# Cap_Sensor_Hand.net
KiCad netlist of a schematic drawn in Altium Designer
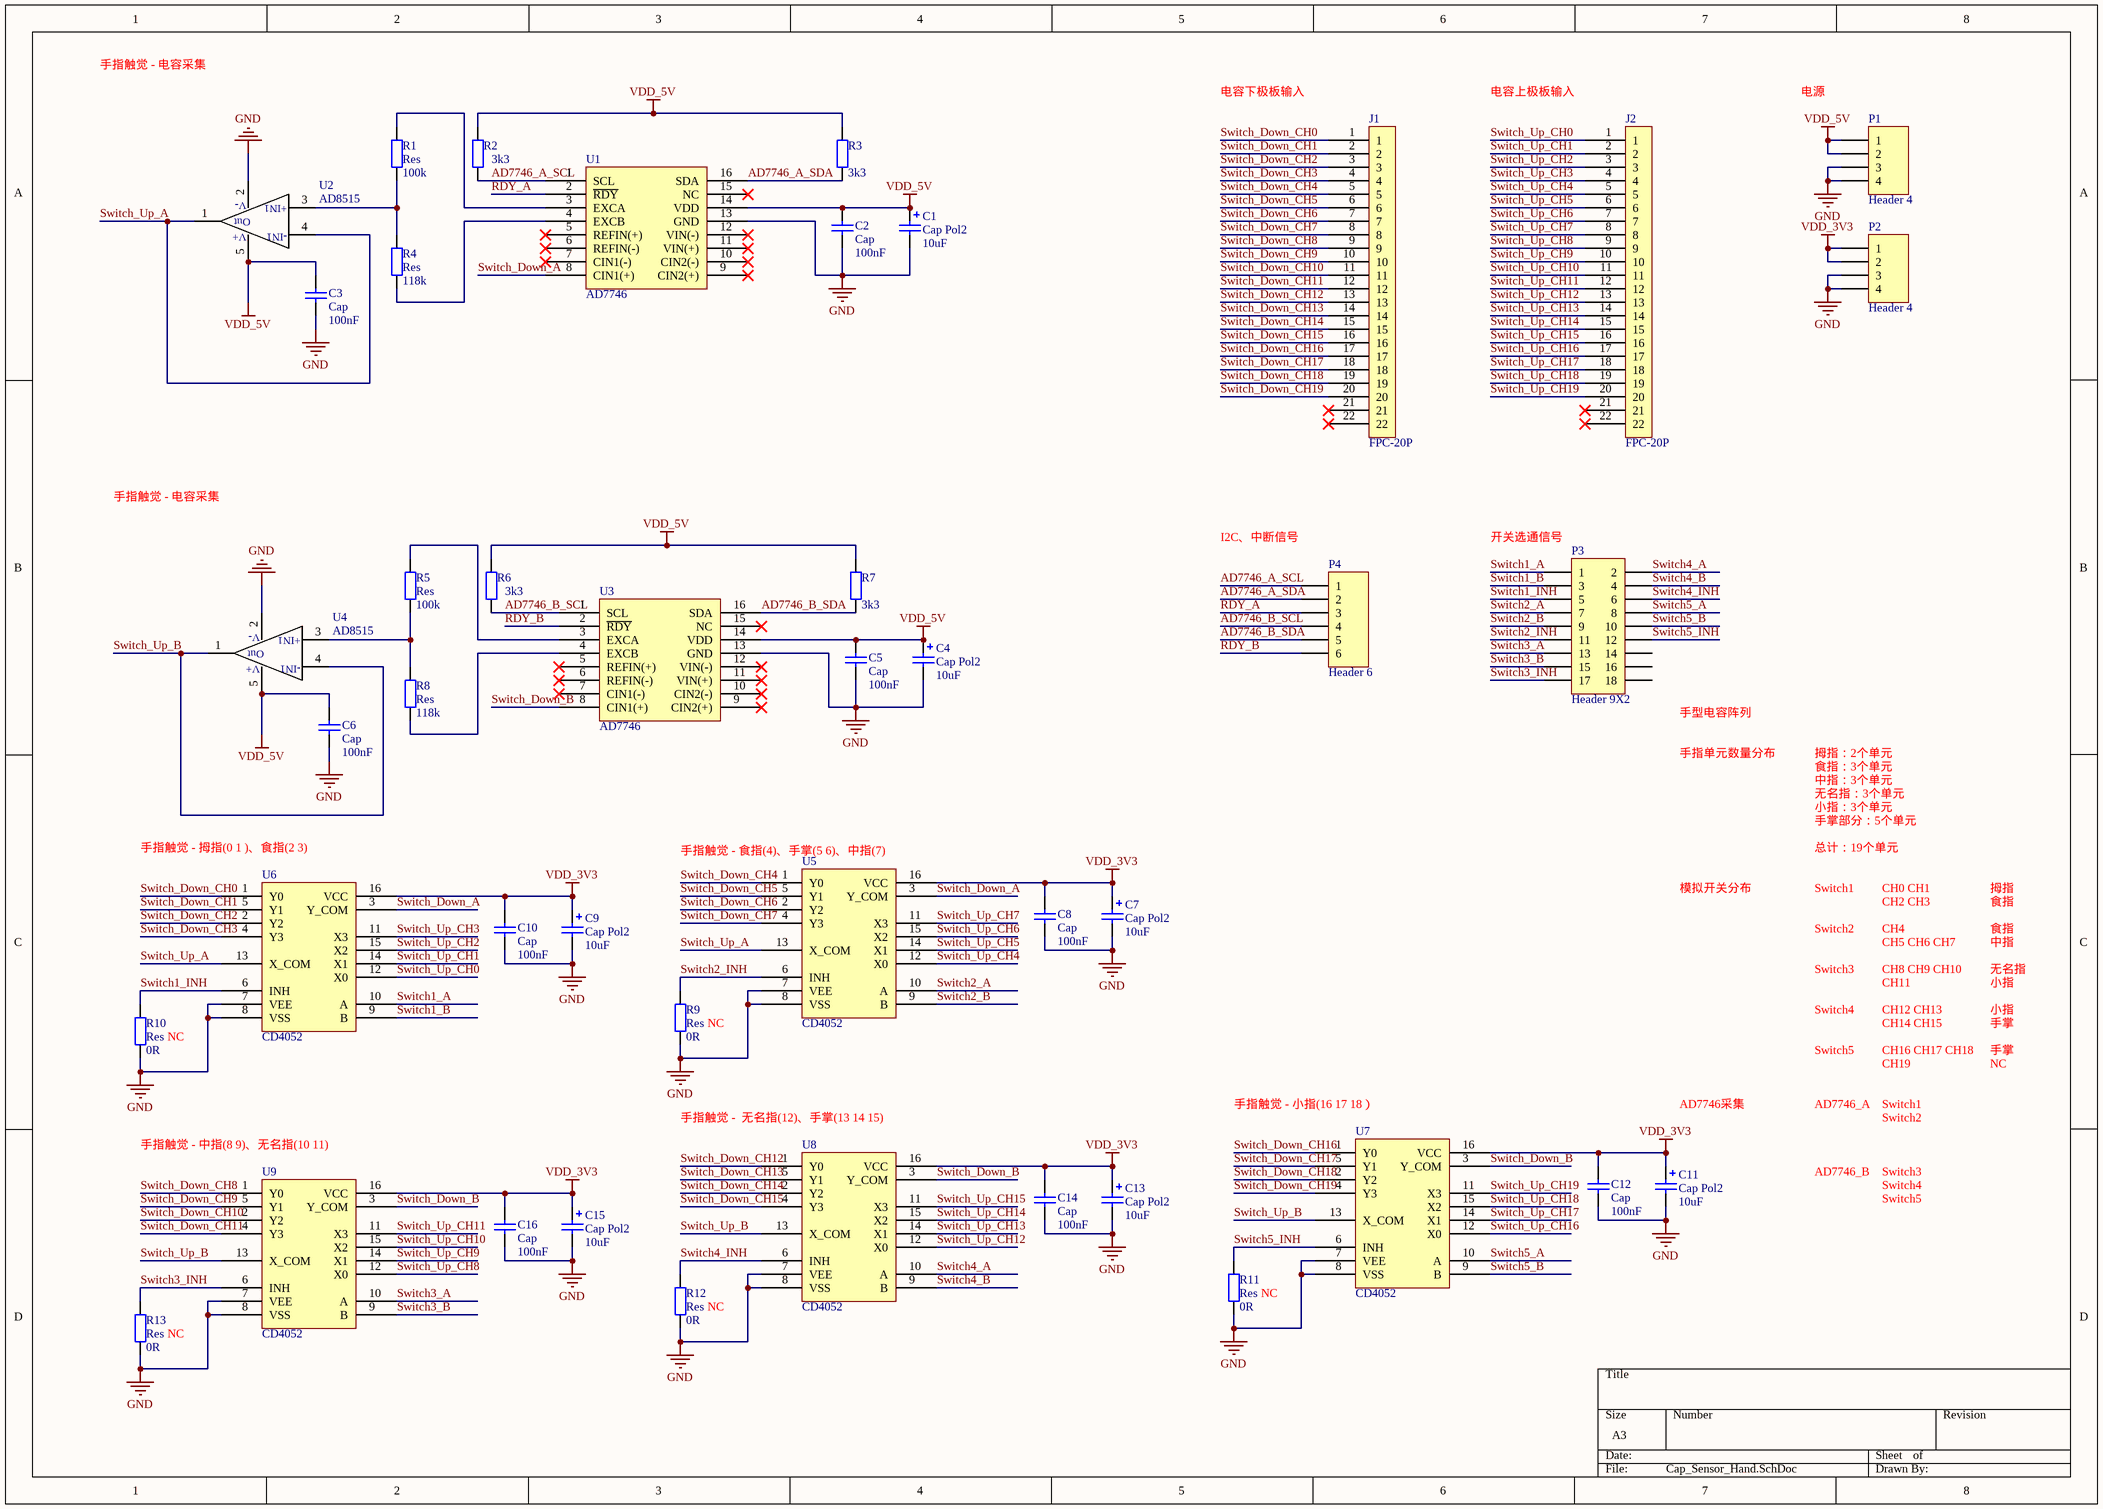
[diagram p0: Cap_Sensor_Hand.SchDoc]

(export (version "E")
  (design (tool "Eeschema 10.0.6"))
  (components
    (comp (ref "C1")
      (value "Cap Pol2")
      (footprint "Cap-TA")
      (description "Polarized Capacitor (Axial)")
      (fields (field (name "ALTIUM_VALUE") "10uF") (field (name "PUBLISHER") "Altium Limited"))
      (libsource (lib "YD-LibrarySCH") (part "Cap Pol2"))
    )
    (comp (ref "C2")
      (value "Cap")
      (footprint "0805C")
      (description "Capacitor")
      (fields (field (name "ALTIUM_VALUE") "100nF") (field (name "PUBLISHER") "Altium Limited"))
      (libsource (lib "YD-LibrarySCH") (part "Cap"))
    )
    (comp (ref "C3")
      (value "Cap")
      (footprint "0805C")
      (description "Capacitor")
      (fields (field (name "ALTIUM_VALUE") "100nF") (field (name "PUBLISHER") "Altium Limited"))
      (libsource (lib "YD-LibrarySCH") (part "Cap"))
    )
    (comp (ref "C4")
      (value "Cap Pol2")
      (footprint "Cap-TA")
      (description "Polarized Capacitor (Axial)")
      (fields (field (name "ALTIUM_VALUE") "10uF") (field (name "PUBLISHER") "Altium Limited"))
      (libsource (lib "YD-LibrarySCH") (part "Cap Pol2"))
    )
    (comp (ref "C5")
      (value "Cap")
      (footprint "0805C")
      (description "Capacitor")
      (fields (field (name "ALTIUM_VALUE") "100nF") (field (name "PUBLISHER") "Altium Limited"))
      (libsource (lib "YD-LibrarySCH") (part "Cap"))
    )
    (comp (ref "C6")
      (value "Cap")
      (footprint "0805C")
      (description "Capacitor")
      (fields (field (name "ALTIUM_VALUE") "100nF") (field (name "PUBLISHER") "Altium Limited"))
      (libsource (lib "YD-LibrarySCH") (part "Cap"))
    )
    (comp (ref "C7")
      (value "Cap Pol2")
      (footprint "Cap-TA")
      (description "Polarized Capacitor (Axial)")
      (fields (field (name "ALTIUM_VALUE") "10uF") (field (name "PUBLISHER") "Altium Limited"))
      (libsource (lib "YD-LibrarySCH") (part "Cap Pol2"))
    )
    (comp (ref "C8")
      (value "Cap")
      (footprint "0805C")
      (description "Capacitor")
      (fields (field (name "ALTIUM_VALUE") "100nF") (field (name "PUBLISHER") "Altium Limited"))
      (libsource (lib "YD-LibrarySCH") (part "Cap"))
    )
    (comp (ref "C9")
      (value "Cap Pol2")
      (footprint "Cap-TA")
      (description "Polarized Capacitor (Axial)")
      (fields (field (name "ALTIUM_VALUE") "10uF") (field (name "PUBLISHER") "Altium Limited"))
      (libsource (lib "YD-LibrarySCH") (part "Cap Pol2"))
    )
    (comp (ref "C10")
      (value "Cap")
      (footprint "0805C")
      (description "Capacitor")
      (fields (field (name "ALTIUM_VALUE") "100nF") (field (name "PUBLISHER") "Altium Limited"))
      (libsource (lib "YD-LibrarySCH") (part "Cap"))
    )
    (comp (ref "C11")
      (value "Cap Pol2")
      (footprint "Cap-TA")
      (description "Polarized Capacitor (Axial)")
      (fields (field (name "ALTIUM_VALUE") "10uF") (field (name "PUBLISHER") "Altium Limited"))
      (libsource (lib "YD-LibrarySCH") (part "Cap Pol2"))
    )
    (comp (ref "C12")
      (value "Cap")
      (footprint "0805C")
      (description "Capacitor")
      (fields (field (name "ALTIUM_VALUE") "100nF") (field (name "PUBLISHER") "Altium Limited"))
      (libsource (lib "YD-LibrarySCH") (part "Cap"))
    )
    (comp (ref "C13")
      (value "Cap Pol2")
      (footprint "Cap-TA")
      (description "Polarized Capacitor (Axial)")
      (fields (field (name "ALTIUM_VALUE") "10uF") (field (name "PUBLISHER") "Altium Limited"))
      (libsource (lib "YD-LibrarySCH") (part "Cap Pol2"))
    )
    (comp (ref "C14")
      (value "Cap")
      (footprint "0805C")
      (description "Capacitor")
      (fields (field (name "ALTIUM_VALUE") "100nF") (field (name "PUBLISHER") "Altium Limited"))
      (libsource (lib "YD-LibrarySCH") (part "Cap"))
    )
    (comp (ref "C15")
      (value "Cap Pol2")
      (footprint "Cap-TA")
      (description "Polarized Capacitor (Axial)")
      (fields (field (name "ALTIUM_VALUE") "10uF") (field (name "PUBLISHER") "Altium Limited"))
      (libsource (lib "YD-LibrarySCH") (part "Cap Pol2"))
    )
    (comp (ref "C16")
      (value "Cap")
      (footprint "0805C")
      (description "Capacitor")
      (fields (field (name "ALTIUM_VALUE") "100nF") (field (name "PUBLISHER") "Altium Limited"))
      (libsource (lib "YD-LibrarySCH") (part "Cap"))
    )
    (comp (ref "J1")
      (value "FPC-20P")
      (footprint "FPC20-0.5")
      (libsource (lib "YD-LibrarySCH") (part "FPC_20P"))
    )
    (comp (ref "J2")
      (value "FPC-20P")
      (footprint "FPC20-0.5")
      (libsource (lib "YD-LibrarySCH") (part "FPC_20P"))
    )
    (comp (ref "P1")
      (value "Header 4")
      (footprint "HDR1X4")
      (description "Header, 4-Pin")
      (fields (field (name "PUBLISHER") "Altium Limited"))
      (libsource (lib "YD-LibrarySCH") (part "Header 4"))
    )
    (comp (ref "P2")
      (value "Header 4")
      (footprint "HDR1X4")
      (description "Header, 4-Pin")
      (fields (field (name "PUBLISHER") "Altium Limited"))
      (libsource (lib "YD-LibrarySCH") (part "Header 4"))
    )
    (comp (ref "P3")
      (value "Header 9X2")
      (footprint "HDR2X9")
      (description "Header, 9-Pin, Dual row")
      (fields (field (name "PUBLISHER") "Altium Limited"))
      (libsource (lib "YD-LibrarySCH") (part "Header 9X2"))
    )
    (comp (ref "P4")
      (value "Header 6")
      (footprint "HDR1X6")
      (description "Header, 6-Pin")
      (fields (field (name "PUBLISHER") "Altium Limited"))
      (libsource (lib "YD-LibrarySCH") (part "Header 6"))
    )
    (comp (ref "R1")
      (value "Res")
      (footprint "0805R")
      (description "Resistor")
      (fields (field (name "ALTIUM_VALUE") "100k") (field (name "PUBLISHER") "Altium Limited"))
      (libsource (lib "") (part "Res_1"))
    )
    (comp (ref "R2")
      (value "3k3")
      (footprint "0805R")
      (description "Resistor")
      (fields (field (name "Comment") "Res") (field (name "PUBLISHER") "Altium Limited"))
      (libsource (lib "YD-LibrarySCH") (part "Res"))
    )
    (comp (ref "R3")
      (value "3k3")
      (footprint "0805R")
      (description "Resistor")
      (fields (field (name "Comment") "Res") (field (name "PUBLISHER") "Altium Limited"))
      (libsource (lib "YD-LibrarySCH") (part "Res"))
    )
    (comp (ref "R4")
      (value "Res")
      (footprint "0805R")
      (description "Resistor")
      (fields (field (name "ALTIUM_VALUE") "118k") (field (name "PUBLISHER") "Altium Limited"))
      (libsource (lib "") (part "Res_1"))
    )
    (comp (ref "R5")
      (value "Res")
      (footprint "0805R")
      (description "Resistor")
      (fields (field (name "ALTIUM_VALUE") "100k") (field (name "PUBLISHER") "Altium Limited"))
      (libsource (lib "") (part "Res_1"))
    )
    (comp (ref "R6")
      (value "3k3")
      (footprint "0805R")
      (description "Resistor")
      (fields (field (name "Comment") "Res") (field (name "PUBLISHER") "Altium Limited"))
      (libsource (lib "YD-LibrarySCH") (part "Res"))
    )
    (comp (ref "R7")
      (value "3k3")
      (footprint "0805R")
      (description "Resistor")
      (fields (field (name "Comment") "Res") (field (name "PUBLISHER") "Altium Limited"))
      (libsource (lib "YD-LibrarySCH") (part "Res"))
    )
    (comp (ref "R8")
      (value "Res")
      (footprint "0805R")
      (description "Resistor")
      (fields (field (name "ALTIUM_VALUE") "118k") (field (name "PUBLISHER") "Altium Limited"))
      (libsource (lib "") (part "Res_1"))
    )
    (comp (ref "R9")
      (value "Res")
      (footprint "0805R")
      (description "Resistor")
      (fields (field (name "ALTIUM_VALUE") "0R") (field (name "PUBLISHER") "Altium Limited"))
      (libsource (lib "") (part "Res_1"))
    )
    (comp (ref "R10")
      (value "Res")
      (footprint "0805R")
      (description "Resistor")
      (fields (field (name "ALTIUM_VALUE") "0R") (field (name "PUBLISHER") "Altium Limited"))
      (libsource (lib "") (part "Res_1"))
    )
    (comp (ref "R11")
      (value "Res")
      (footprint "0805R")
      (description "Resistor")
      (fields (field (name "ALTIUM_VALUE") "0R") (field (name "PUBLISHER") "Altium Limited"))
      (libsource (lib "") (part "Res_1"))
    )
    (comp (ref "R12")
      (value "Res")
      (footprint "0805R")
      (description "Resistor")
      (fields (field (name "ALTIUM_VALUE") "0R") (field (name "PUBLISHER") "Altium Limited"))
      (libsource (lib "") (part "Res_1"))
    )
    (comp (ref "R13")
      (value "Res")
      (footprint "0805R")
      (description "Resistor")
      (fields (field (name "ALTIUM_VALUE") "0R") (field (name "PUBLISHER") "Altium Limited"))
      (libsource (lib "") (part "Res_1"))
    )
    (comp (ref "U1") (value "AD7746") (footprint "TSSOP16") (libsource (lib "YD-LibrarySCH") (part "AD7746")))
    (comp (ref "U2") (value "AD8515") (footprint "sot23-5") (libsource (lib "YD-LibrarySCH") (part "AD8515")))
    (comp (ref "U3") (value "AD7746") (footprint "TSSOP16") (libsource (lib "YD-LibrarySCH") (part "AD7746")))
    (comp (ref "U4") (value "AD8515") (footprint "sot23-5") (libsource (lib "YD-LibrarySCH") (part "AD8515")))
    (comp (ref "U5") (value "CD4052") (footprint "sop16") (libsource (lib "YD-LibrarySCH") (part "CD4052")))
    (comp (ref "U6") (value "CD4052") (footprint "SOP16") (libsource (lib "YD-LibrarySCH") (part "CD4052")))
    (comp (ref "U7") (value "CD4052") (footprint "sop16") (libsource (lib "YD-LibrarySCH") (part "CD4052")))
    (comp (ref "U8") (value "CD4052") (footprint "sop16") (libsource (lib "YD-LibrarySCH") (part "CD4052")))
    (comp (ref "U9") (value "CD4052") (footprint "sop16") (libsource (lib "YD-LibrarySCH") (part "CD4052")))
  )
  (nets
    (net (code "1") (name "/AD7746_A_SCL") (class "Default")
      (node (ref "P4") (pin "1") (pinfunction "1_1") (pintype "passive"))
      (node (ref "R2") (pin "1") (pinfunction "1_1") (pintype "passive"))
      (node (ref "U1") (pin "1") (pinfunction "SCL_1") (pintype "passive"))
    )
    (net (code "2") (name "/AD7746_A_SDA") (class "Default")
      (node (ref "P4") (pin "2") (pinfunction "2_2") (pintype "passive"))
      (node (ref "R3") (pin "1") (pinfunction "1_1") (pintype "passive"))
      (node (ref "U1") (pin "16") (pinfunction "SDA_16") (pintype "passive"))
    )
    (net (code "3") (name "/AD7746_B_SCL") (class "Default")
      (node (ref "P4") (pin "4") (pinfunction "4_4") (pintype "passive"))
      (node (ref "R6") (pin "1") (pinfunction "1_1") (pintype "passive"))
      (node (ref "U3") (pin "1") (pinfunction "SCL_1") (pintype "passive"))
    )
    (net (code "4") (name "/AD7746_B_SDA") (class "Default")
      (node (ref "P4") (pin "5") (pinfunction "5_5") (pintype "passive"))
      (node (ref "R7") (pin "1") (pinfunction "1_1") (pintype "passive"))
      (node (ref "U3") (pin "16") (pinfunction "SDA_16") (pintype "passive"))
    )
    (net (code "5") (name "/RDY_A") (class "Default")
      (node (ref "P4") (pin "3") (pinfunction "3_3") (pintype "passive"))
      (node (ref "U1") (pin "2") (pinfunction "~{RDY}_2") (pintype "passive"))
    )
    (net (code "6") (name "/RDY_B") (class "Default")
      (node (ref "P4") (pin "6") (pinfunction "6_6") (pintype "passive"))
      (node (ref "U3") (pin "2") (pinfunction "~{RDY}_2") (pintype "passive"))
    )
    (net (code "7") (name "/Switch1_A") (class "Default")
      (node (ref "P3") (pin "1") (pinfunction "1_1") (pintype "passive"))
      (node (ref "U6") (pin "10") (pinfunction "A_10") (pintype "passive"))
    )
    (net (code "8") (name "/Switch1_B") (class "Default")
      (node (ref "P3") (pin "3") (pinfunction "3_3") (pintype "passive"))
      (node (ref "U6") (pin "9") (pinfunction "B_9") (pintype "passive"))
    )
    (net (code "9") (name "/Switch1_INH") (class "Default")
      (node (ref "P3") (pin "5") (pinfunction "5_5") (pintype "passive"))
      (node (ref "R10") (pin "1") (pinfunction "1_1") (pintype "passive"))
      (node (ref "U6") (pin "6") (pinfunction "INH_6") (pintype "passive"))
    )
    (net (code "10") (name "/Switch2_A") (class "Default")
      (node (ref "P3") (pin "7") (pinfunction "7_7") (pintype "passive"))
      (node (ref "U5") (pin "10") (pinfunction "A_10") (pintype "passive"))
    )
    (net (code "11") (name "/Switch2_B") (class "Default")
      (node (ref "P3") (pin "9") (pinfunction "9_9") (pintype "passive"))
      (node (ref "U5") (pin "9") (pinfunction "B_9") (pintype "passive"))
    )
    (net (code "12") (name "/Switch2_INH") (class "Default")
      (node (ref "P3") (pin "11") (pinfunction "11_11") (pintype "passive"))
      (node (ref "R9") (pin "1") (pinfunction "1_1") (pintype "passive"))
      (node (ref "U5") (pin "6") (pinfunction "INH_6") (pintype "passive"))
    )
    (net (code "13") (name "/Switch3_A") (class "Default")
      (node (ref "P3") (pin "13") (pinfunction "13_13") (pintype "passive"))
      (node (ref "U9") (pin "10") (pinfunction "A_10") (pintype "passive"))
    )
    (net (code "14") (name "/Switch3_B") (class "Default")
      (node (ref "P3") (pin "15") (pinfunction "15_15") (pintype "passive"))
      (node (ref "U9") (pin "9") (pinfunction "B_9") (pintype "passive"))
    )
    (net (code "15") (name "/Switch3_INH") (class "Default")
      (node (ref "P3") (pin "17") (pinfunction "17_17") (pintype "passive"))
      (node (ref "R13") (pin "1") (pinfunction "1_1") (pintype "passive"))
      (node (ref "U9") (pin "6") (pinfunction "INH_6") (pintype "passive"))
    )
    (net (code "16") (name "/Switch4_A") (class "Default")
      (node (ref "P3") (pin "2") (pinfunction "2_2") (pintype "passive"))
      (node (ref "U8") (pin "10") (pinfunction "A_10") (pintype "passive"))
    )
    (net (code "17") (name "/Switch4_B") (class "Default")
      (node (ref "P3") (pin "4") (pinfunction "4_4") (pintype "passive"))
      (node (ref "U8") (pin "9") (pinfunction "B_9") (pintype "passive"))
    )
    (net (code "18") (name "/Switch4_INH") (class "Default")
      (node (ref "P3") (pin "6") (pinfunction "6_6") (pintype "passive"))
      (node (ref "R12") (pin "1") (pinfunction "1_1") (pintype "passive"))
      (node (ref "U8") (pin "6") (pinfunction "INH_6") (pintype "passive"))
    )
    (net (code "19") (name "/Switch5_A") (class "Default")
      (node (ref "P3") (pin "8") (pinfunction "8_8") (pintype "passive"))
      (node (ref "U7") (pin "10") (pinfunction "A_10") (pintype "passive"))
    )
    (net (code "20") (name "/Switch5_B") (class "Default")
      (node (ref "P3") (pin "10") (pinfunction "10_10") (pintype "passive"))
      (node (ref "U7") (pin "9") (pinfunction "B_9") (pintype "passive"))
    )
    (net (code "21") (name "/Switch5_INH") (class "Default")
      (node (ref "P3") (pin "12") (pinfunction "12_12") (pintype "passive"))
      (node (ref "R11") (pin "1") (pinfunction "1_1") (pintype "passive"))
      (node (ref "U7") (pin "6") (pinfunction "INH_6") (pintype "passive"))
    )
    (net (code "22") (name "/Switch_Down_A") (class "Default")
      (node (ref "U1") (pin "8") (pinfunction "CIN1(+)_8") (pintype "passive"))
      (node (ref "U5") (pin "3") (pinfunction "Y_COM_3") (pintype "passive"))
      (node (ref "U6") (pin "3") (pinfunction "Y_COM_3") (pintype "passive"))
    )
    (net (code "23") (name "/Switch_Down_B") (class "Default")
      (node (ref "U3") (pin "8") (pinfunction "CIN1(+)_8") (pintype "passive"))
      (node (ref "U7") (pin "3") (pinfunction "Y_COM_3") (pintype "passive"))
      (node (ref "U8") (pin "3") (pinfunction "Y_COM_3") (pintype "passive"))
      (node (ref "U9") (pin "3") (pinfunction "Y_COM_3") (pintype "passive"))
    )
    (net (code "24") (name "/Switch_Down_CH0") (class "Default")
      (node (ref "J1") (pin "1") (pinfunction "1_1") (pintype "passive"))
      (node (ref "U6") (pin "1") (pinfunction "Y0_1") (pintype "passive"))
    )
    (net (code "25") (name "/Switch_Down_CH1") (class "Default")
      (node (ref "J1") (pin "2") (pinfunction "2_2") (pintype "passive"))
      (node (ref "U6") (pin "5") (pinfunction "Y1_5") (pintype "passive"))
    )
    (net (code "26") (name "/Switch_Down_CH2") (class "Default")
      (node (ref "J1") (pin "3") (pinfunction "3_3") (pintype "passive"))
      (node (ref "U6") (pin "2") (pinfunction "Y2_2") (pintype "passive"))
    )
    (net (code "27") (name "/Switch_Down_CH3") (class "Default")
      (node (ref "J1") (pin "4") (pinfunction "4_4") (pintype "passive"))
      (node (ref "U6") (pin "4") (pinfunction "Y3_4") (pintype "passive"))
    )
    (net (code "28") (name "/Switch_Down_CH4") (class "Default")
      (node (ref "J1") (pin "5") (pinfunction "5_5") (pintype "passive"))
      (node (ref "U5") (pin "1") (pinfunction "Y0_1") (pintype "passive"))
    )
    (net (code "29") (name "/Switch_Down_CH5") (class "Default")
      (node (ref "J1") (pin "6") (pinfunction "6_6") (pintype "passive"))
      (node (ref "U5") (pin "5") (pinfunction "Y1_5") (pintype "passive"))
    )
    (net (code "30") (name "/Switch_Down_CH6") (class "Default")
      (node (ref "J1") (pin "7") (pinfunction "7_7") (pintype "passive"))
      (node (ref "U5") (pin "2") (pinfunction "Y2_2") (pintype "passive"))
    )
    (net (code "31") (name "/Switch_Down_CH7") (class "Default")
      (node (ref "J1") (pin "8") (pinfunction "8_8") (pintype "passive"))
      (node (ref "U5") (pin "4") (pinfunction "Y3_4") (pintype "passive"))
    )
    (net (code "32") (name "/Switch_Down_CH8") (class "Default")
      (node (ref "J1") (pin "9") (pinfunction "9_9") (pintype "passive"))
      (node (ref "U9") (pin "1") (pinfunction "Y0_1") (pintype "passive"))
    )
    (net (code "33") (name "/Switch_Down_CH9") (class "Default")
      (node (ref "J1") (pin "10") (pinfunction "10_10") (pintype "passive"))
      (node (ref "U9") (pin "5") (pinfunction "Y1_5") (pintype "passive"))
    )
    (net (code "34") (name "/Switch_Down_CH10") (class "Default")
      (node (ref "J1") (pin "11") (pinfunction "11_11") (pintype "passive"))
      (node (ref "U9") (pin "2") (pinfunction "Y2_2") (pintype "passive"))
    )
    (net (code "35") (name "/Switch_Down_CH11") (class "Default")
      (node (ref "J1") (pin "12") (pinfunction "12_12") (pintype "passive"))
      (node (ref "U9") (pin "4") (pinfunction "Y3_4") (pintype "passive"))
    )
    (net (code "36") (name "/Switch_Down_CH12") (class "Default")
      (node (ref "J1") (pin "13") (pinfunction "13_13") (pintype "passive"))
      (node (ref "U8") (pin "1") (pinfunction "Y0_1") (pintype "passive"))
    )
    (net (code "37") (name "/Switch_Down_CH13") (class "Default")
      (node (ref "J1") (pin "14") (pinfunction "14_14") (pintype "passive"))
      (node (ref "U8") (pin "5") (pinfunction "Y1_5") (pintype "passive"))
    )
    (net (code "38") (name "/Switch_Down_CH14") (class "Default")
      (node (ref "J1") (pin "15") (pinfunction "15_15") (pintype "passive"))
      (node (ref "U8") (pin "2") (pinfunction "Y2_2") (pintype "passive"))
    )
    (net (code "39") (name "/Switch_Down_CH15") (class "Default")
      (node (ref "J1") (pin "16") (pinfunction "16_16") (pintype "passive"))
      (node (ref "U8") (pin "4") (pinfunction "Y3_4") (pintype "passive"))
    )
    (net (code "40") (name "/Switch_Down_CH16") (class "Default")
      (node (ref "J1") (pin "17") (pinfunction "17_17") (pintype "passive"))
      (node (ref "U7") (pin "1") (pinfunction "Y0_1") (pintype "passive"))
    )
    (net (code "41") (name "/Switch_Down_CH17") (class "Default")
      (node (ref "J1") (pin "18") (pinfunction "18_18") (pintype "passive"))
      (node (ref "U7") (pin "5") (pinfunction "Y1_5") (pintype "passive"))
    )
    (net (code "42") (name "/Switch_Down_CH18") (class "Default")
      (node (ref "J1") (pin "19") (pinfunction "19_19") (pintype "passive"))
      (node (ref "U7") (pin "2") (pinfunction "Y2_2") (pintype "passive"))
    )
    (net (code "43") (name "/Switch_Down_CH19") (class "Default")
      (node (ref "J1") (pin "20") (pinfunction "20_20") (pintype "passive"))
      (node (ref "U7") (pin "4") (pinfunction "Y3_4") (pintype "passive"))
    )
    (net (code "44") (name "/Switch_Up_A") (class "Default")
      (node (ref "U2") (pin "1") (pinfunction "Out1_1") (pintype "passive"))
      (node (ref "U2") (pin "4") (pinfunction "-IN_4") (pintype "passive"))
      (node (ref "U5") (pin "13") (pinfunction "X_COM_13") (pintype "passive"))
      (node (ref "U6") (pin "13") (pinfunction "X_COM_13") (pintype "passive"))
    )
    (net (code "45") (name "/Switch_Up_B") (class "Default")
      (node (ref "U4") (pin "1") (pinfunction "Out1_1") (pintype "passive"))
      (node (ref "U4") (pin "4") (pinfunction "-IN_4") (pintype "passive"))
      (node (ref "U7") (pin "13") (pinfunction "X_COM_13") (pintype "passive"))
      (node (ref "U8") (pin "13") (pinfunction "X_COM_13") (pintype "passive"))
      (node (ref "U9") (pin "13") (pinfunction "X_COM_13") (pintype "passive"))
    )
    (net (code "46") (name "/Switch_Up_CH0") (class "Default")
      (node (ref "J2") (pin "1") (pinfunction "1_1") (pintype "passive"))
      (node (ref "U6") (pin "12") (pinfunction "X0_12") (pintype "passive"))
    )
    (net (code "47") (name "/Switch_Up_CH1") (class "Default")
      (node (ref "J2") (pin "2") (pinfunction "2_2") (pintype "passive"))
      (node (ref "U6") (pin "14") (pinfunction "X1_14") (pintype "passive"))
    )
    (net (code "48") (name "/Switch_Up_CH2") (class "Default")
      (node (ref "J2") (pin "3") (pinfunction "3_3") (pintype "passive"))
      (node (ref "U6") (pin "15") (pinfunction "X2_15") (pintype "passive"))
    )
    (net (code "49") (name "/Switch_Up_CH3") (class "Default")
      (node (ref "J2") (pin "4") (pinfunction "4_4") (pintype "passive"))
      (node (ref "U6") (pin "11") (pinfunction "X3_11") (pintype "passive"))
    )
    (net (code "50") (name "/Switch_Up_CH4") (class "Default")
      (node (ref "J2") (pin "5") (pinfunction "5_5") (pintype "passive"))
      (node (ref "U5") (pin "12") (pinfunction "X0_12") (pintype "passive"))
    )
    (net (code "51") (name "/Switch_Up_CH5") (class "Default")
      (node (ref "J2") (pin "6") (pinfunction "6_6") (pintype "passive"))
      (node (ref "U5") (pin "14") (pinfunction "X1_14") (pintype "passive"))
    )
    (net (code "52") (name "/Switch_Up_CH6") (class "Default")
      (node (ref "J2") (pin "7") (pinfunction "7_7") (pintype "passive"))
      (node (ref "U5") (pin "15") (pinfunction "X2_15") (pintype "passive"))
    )
    (net (code "53") (name "/Switch_Up_CH7") (class "Default")
      (node (ref "J2") (pin "8") (pinfunction "8_8") (pintype "passive"))
      (node (ref "U5") (pin "11") (pinfunction "X3_11") (pintype "passive"))
    )
    (net (code "54") (name "/Switch_Up_CH8") (class "Default")
      (node (ref "J2") (pin "9") (pinfunction "9_9") (pintype "passive"))
      (node (ref "U9") (pin "12") (pinfunction "X0_12") (pintype "passive"))
    )
    (net (code "55") (name "/Switch_Up_CH9") (class "Default")
      (node (ref "J2") (pin "10") (pinfunction "10_10") (pintype "passive"))
      (node (ref "U9") (pin "14") (pinfunction "X1_14") (pintype "passive"))
    )
    (net (code "56") (name "/Switch_Up_CH10") (class "Default")
      (node (ref "J2") (pin "11") (pinfunction "11_11") (pintype "passive"))
      (node (ref "U9") (pin "15") (pinfunction "X2_15") (pintype "passive"))
    )
    (net (code "57") (name "/Switch_Up_CH11") (class "Default")
      (node (ref "J2") (pin "12") (pinfunction "12_12") (pintype "passive"))
      (node (ref "U9") (pin "11") (pinfunction "X3_11") (pintype "passive"))
    )
    (net (code "58") (name "/Switch_Up_CH12") (class "Default")
      (node (ref "J2") (pin "13") (pinfunction "13_13") (pintype "passive"))
      (node (ref "U8") (pin "12") (pinfunction "X0_12") (pintype "passive"))
    )
    (net (code "59") (name "/Switch_Up_CH13") (class "Default")
      (node (ref "J2") (pin "14") (pinfunction "14_14") (pintype "passive"))
      (node (ref "U8") (pin "14") (pinfunction "X1_14") (pintype "passive"))
    )
    (net (code "60") (name "/Switch_Up_CH14") (class "Default")
      (node (ref "J2") (pin "15") (pinfunction "15_15") (pintype "passive"))
      (node (ref "U8") (pin "15") (pinfunction "X2_15") (pintype "passive"))
    )
    (net (code "61") (name "/Switch_Up_CH15") (class "Default")
      (node (ref "J2") (pin "16") (pinfunction "16_16") (pintype "passive"))
      (node (ref "U8") (pin "11") (pinfunction "X3_11") (pintype "passive"))
    )
    (net (code "62") (name "/Switch_Up_CH16") (class "Default")
      (node (ref "J2") (pin "17") (pinfunction "17_17") (pintype "passive"))
      (node (ref "U7") (pin "12") (pinfunction "X0_12") (pintype "passive"))
    )
    (net (code "63") (name "/Switch_Up_CH17") (class "Default")
      (node (ref "J2") (pin "18") (pinfunction "18_18") (pintype "passive"))
      (node (ref "U7") (pin "14") (pinfunction "X1_14") (pintype "passive"))
    )
    (net (code "64") (name "/Switch_Up_CH18") (class "Default")
      (node (ref "J2") (pin "19") (pinfunction "19_19") (pintype "passive"))
      (node (ref "U7") (pin "15") (pinfunction "X2_15") (pintype "passive"))
    )
    (net (code "65") (name "/Switch_Up_CH19") (class "Default")
      (node (ref "J2") (pin "20") (pinfunction "20_20") (pintype "passive"))
      (node (ref "U7") (pin "11") (pinfunction "X3_11") (pintype "passive"))
    )
    (net (code "66") (name "GND") (class "Default")
      (node (ref "C1") (pin "2") (pinfunction "2_2") (pintype "passive"))
      (node (ref "C10") (pin "1") (pinfunction "1_1") (pintype "passive"))
      (node (ref "C11") (pin "2") (pinfunction "2_2") (pintype "passive"))
      (node (ref "C12") (pin "1") (pinfunction "1_1") (pintype "passive"))
      (node (ref "C13") (pin "2") (pinfunction "2_2") (pintype "passive"))
      (node (ref "C14") (pin "1") (pinfunction "1_1") (pintype "passive"))
      (node (ref "C15") (pin "2") (pinfunction "2_2") (pintype "passive"))
      (node (ref "C16") (pin "1") (pinfunction "1_1") (pintype "passive"))
      (node (ref "C2") (pin "1") (pinfunction "1_1") (pintype "passive"))
      (node (ref "C3") (pin "1") (pinfunction "1_1") (pintype "passive"))
      (node (ref "C4") (pin "2") (pinfunction "2_2") (pintype "passive"))
      (node (ref "C5") (pin "1") (pinfunction "1_1") (pintype "passive"))
      (node (ref "C6") (pin "1") (pinfunction "1_1") (pintype "passive"))
      (node (ref "C7") (pin "2") (pinfunction "2_2") (pintype "passive"))
      (node (ref "C8") (pin "1") (pinfunction "1_1") (pintype "passive"))
      (node (ref "C9") (pin "2") (pinfunction "2_2") (pintype "passive"))
      (node (ref "P1") (pin "3") (pinfunction "3_3") (pintype "passive"))
      (node (ref "P1") (pin "4") (pinfunction "4_4") (pintype "passive"))
      (node (ref "P2") (pin "3") (pinfunction "3_3") (pintype "passive"))
      (node (ref "P2") (pin "4") (pinfunction "4_4") (pintype "passive"))
      (node (ref "R10") (pin "2") (pinfunction "2_2") (pintype "passive"))
      (node (ref "R11") (pin "2") (pinfunction "2_2") (pintype "passive"))
      (node (ref "R12") (pin "2") (pinfunction "2_2") (pintype "passive"))
      (node (ref "R13") (pin "2") (pinfunction "2_2") (pintype "passive"))
      (node (ref "R9") (pin "2") (pinfunction "2_2") (pintype "passive"))
      (node (ref "U1") (pin "13") (pinfunction "GND_13") (pintype "passive"))
      (node (ref "U2") (pin "2") (pinfunction "V-_2") (pintype "passive"))
      (node (ref "U3") (pin "13") (pinfunction "GND_13") (pintype "passive"))
      (node (ref "U4") (pin "2") (pinfunction "V-_2") (pintype "passive"))
      (node (ref "U5") (pin "7") (pinfunction "VEE_7") (pintype "passive"))
      (node (ref "U5") (pin "8") (pinfunction "VSS_8") (pintype "passive"))
      (node (ref "U6") (pin "7") (pinfunction "VEE_7") (pintype "passive"))
      (node (ref "U6") (pin "8") (pinfunction "VSS_8") (pintype "passive"))
      (node (ref "U7") (pin "7") (pinfunction "VEE_7") (pintype "passive"))
      (node (ref "U7") (pin "8") (pinfunction "VSS_8") (pintype "passive"))
      (node (ref "U8") (pin "7") (pinfunction "VEE_7") (pintype "passive"))
      (node (ref "U8") (pin "8") (pinfunction "VSS_8") (pintype "passive"))
      (node (ref "U9") (pin "7") (pinfunction "VEE_7") (pintype "passive"))
      (node (ref "U9") (pin "8") (pinfunction "VSS_8") (pintype "passive"))
    )
    (net (code "67") (name "Net-(U1-EXCA)") (class "Default")
      (node (ref "R1") (pin "1") (pinfunction "1_1") (pintype "passive"))
      (node (ref "U1") (pin "3") (pinfunction "EXCA_3") (pintype "passive"))
    )
    (net (code "68") (name "Net-(U1-EXCB)") (class "Default")
      (node (ref "R4") (pin "2") (pinfunction "2_2") (pintype "passive"))
      (node (ref "U1") (pin "4") (pinfunction "EXCB_4") (pintype "passive"))
    )
    (net (code "69") (name "Net-(U2-+IN)") (class "Default")
      (node (ref "R1") (pin "2") (pinfunction "2_2") (pintype "passive"))
      (node (ref "R4") (pin "1") (pinfunction "1_1") (pintype "passive"))
      (node (ref "U2") (pin "3") (pinfunction "+IN_3") (pintype "passive"))
    )
    (net (code "70") (name "Net-(U3-EXCA)") (class "Default")
      (node (ref "R5") (pin "1") (pinfunction "1_1") (pintype "passive"))
      (node (ref "U3") (pin "3") (pinfunction "EXCA_3") (pintype "passive"))
    )
    (net (code "71") (name "Net-(U3-EXCB)") (class "Default")
      (node (ref "R8") (pin "2") (pinfunction "2_2") (pintype "passive"))
      (node (ref "U3") (pin "4") (pinfunction "EXCB_4") (pintype "passive"))
    )
    (net (code "72") (name "Net-(U4-+IN)") (class "Default")
      (node (ref "R5") (pin "2") (pinfunction "2_2") (pintype "passive"))
      (node (ref "R8") (pin "1") (pinfunction "1_1") (pintype "passive"))
      (node (ref "U4") (pin "3") (pinfunction "+IN_3") (pintype "passive"))
    )
    (net (code "73") (name "VDD_3V3") (class "Default")
      (node (ref "C10") (pin "2") (pinfunction "2_2") (pintype "passive"))
      (node (ref "C11") (pin "1") (pinfunction "1_1") (pintype "passive"))
      (node (ref "C12") (pin "2") (pinfunction "2_2") (pintype "passive"))
      (node (ref "C13") (pin "1") (pinfunction "1_1") (pintype "passive"))
      (node (ref "C14") (pin "2") (pinfunction "2_2") (pintype "passive"))
      (node (ref "C15") (pin "1") (pinfunction "1_1") (pintype "passive"))
      (node (ref "C16") (pin "2") (pinfunction "2_2") (pintype "passive"))
      (node (ref "C7") (pin "1") (pinfunction "1_1") (pintype "passive"))
      (node (ref "C8") (pin "2") (pinfunction "2_2") (pintype "passive"))
      (node (ref "C9") (pin "1") (pinfunction "1_1") (pintype "passive"))
      (node (ref "P2") (pin "1") (pinfunction "1_1") (pintype "passive"))
      (node (ref "P2") (pin "2") (pinfunction "2_2") (pintype "passive"))
      (node (ref "U5") (pin "16") (pinfunction "VCC_16") (pintype "passive"))
      (node (ref "U6") (pin "16") (pinfunction "VCC_16") (pintype "passive"))
      (node (ref "U7") (pin "16") (pinfunction "VCC_16") (pintype "passive"))
      (node (ref "U8") (pin "16") (pinfunction "VCC_16") (pintype "passive"))
      (node (ref "U9") (pin "16") (pinfunction "VCC_16") (pintype "passive"))
    )
    (net (code "74") (name "VDD_5V") (class "Default")
      (node (ref "C1") (pin "1") (pinfunction "1_1") (pintype "passive"))
      (node (ref "C2") (pin "2") (pinfunction "2_2") (pintype "passive"))
      (node (ref "C3") (pin "2") (pinfunction "2_2") (pintype "passive"))
      (node (ref "C4") (pin "1") (pinfunction "1_1") (pintype "passive"))
      (node (ref "C5") (pin "2") (pinfunction "2_2") (pintype "passive"))
      (node (ref "C6") (pin "2") (pinfunction "2_2") (pintype "passive"))
      (node (ref "P1") (pin "1") (pinfunction "1_1") (pintype "passive"))
      (node (ref "P1") (pin "2") (pinfunction "2_2") (pintype "passive"))
      (node (ref "R2") (pin "2") (pinfunction "2_2") (pintype "passive"))
      (node (ref "R3") (pin "2") (pinfunction "2_2") (pintype "passive"))
      (node (ref "R6") (pin "2") (pinfunction "2_2") (pintype "passive"))
      (node (ref "R7") (pin "2") (pinfunction "2_2") (pintype "passive"))
      (node (ref "U1") (pin "14") (pinfunction "VDD_14") (pintype "passive"))
      (node (ref "U2") (pin "5") (pinfunction "V+_5") (pintype "passive"))
      (node (ref "U3") (pin "14") (pinfunction "VDD_14") (pintype "passive"))
      (node (ref "U4") (pin "5") (pinfunction "V+_5") (pintype "passive"))
    )
    (net (code "75") (name "unconnected-(J1-Pad21)") (class "Default")
      (node (ref "J1") (pin "21") (pinfunction "21_21") (pintype "passive+no_connect"))
    )
    (net (code "76") (name "unconnected-(J1-Pad22)") (class "Default")
      (node (ref "J1") (pin "22") (pinfunction "22_22") (pintype "passive+no_connect"))
    )
    (net (code "77") (name "unconnected-(J2-Pad21)") (class "Default")
      (node (ref "J2") (pin "21") (pinfunction "21_21") (pintype "passive+no_connect"))
    )
    (net (code "78") (name "unconnected-(J2-Pad22)") (class "Default")
      (node (ref "J2") (pin "22") (pinfunction "22_22") (pintype "passive+no_connect"))
    )
    (net (code "79") (name "unconnected-(P3-Pad14)") (class "Default")
      (node (ref "P3") (pin "14") (pinfunction "14_14") (pintype "passive"))
    )
    (net (code "80") (name "unconnected-(P3-Pad16)") (class "Default")
      (node (ref "P3") (pin "16") (pinfunction "16_16") (pintype "passive"))
    )
    (net (code "81") (name "unconnected-(P3-Pad18)") (class "Default")
      (node (ref "P3") (pin "18") (pinfunction "18_18") (pintype "passive"))
    )
    (net (code "82") (name "unconnected-(U1-CIN1(-)-Pad7)") (class "Default")
      (node (ref "U1") (pin "7") (pinfunction "CIN1(-)_7") (pintype "passive+no_connect"))
    )
    (net (code "83") (name "unconnected-(U1-CIN2(+)-Pad9)") (class "Default")
      (node (ref "U1") (pin "9") (pinfunction "CIN2(+)_9") (pintype "passive+no_connect"))
    )
    (net (code "84") (name "unconnected-(U1-CIN2(-)-Pad10)") (class "Default")
      (node (ref "U1") (pin "10") (pinfunction "CIN2(-)_10") (pintype "passive+no_connect"))
    )
    (net (code "85") (name "unconnected-(U1-NC-Pad15)") (class "Default")
      (node (ref "U1") (pin "15") (pinfunction "NC_15") (pintype "passive+no_connect"))
    )
    (net (code "86") (name "unconnected-(U1-REFIN(+)-Pad5)") (class "Default")
      (node (ref "U1") (pin "5") (pinfunction "REFIN(+)_5") (pintype "passive+no_connect"))
    )
    (net (code "87") (name "unconnected-(U1-REFIN(-)-Pad6)") (class "Default")
      (node (ref "U1") (pin "6") (pinfunction "REFIN(-)_6") (pintype "passive+no_connect"))
    )
    (net (code "88") (name "unconnected-(U1-VIN(+)-Pad11)") (class "Default")
      (node (ref "U1") (pin "11") (pinfunction "VIN(+)_11") (pintype "passive+no_connect"))
    )
    (net (code "89") (name "unconnected-(U1-VIN(-)-Pad12)") (class "Default")
      (node (ref "U1") (pin "12") (pinfunction "VIN(-)_12") (pintype "passive+no_connect"))
    )
    (net (code "90") (name "unconnected-(U3-CIN1(-)-Pad7)") (class "Default")
      (node (ref "U3") (pin "7") (pinfunction "CIN1(-)_7") (pintype "passive+no_connect"))
    )
    (net (code "91") (name "unconnected-(U3-CIN2(+)-Pad9)") (class "Default")
      (node (ref "U3") (pin "9") (pinfunction "CIN2(+)_9") (pintype "passive+no_connect"))
    )
    (net (code "92") (name "unconnected-(U3-CIN2(-)-Pad10)") (class "Default")
      (node (ref "U3") (pin "10") (pinfunction "CIN2(-)_10") (pintype "passive+no_connect"))
    )
    (net (code "93") (name "unconnected-(U3-NC-Pad15)") (class "Default")
      (node (ref "U3") (pin "15") (pinfunction "NC_15") (pintype "passive+no_connect"))
    )
    (net (code "94") (name "unconnected-(U3-REFIN(+)-Pad5)") (class "Default")
      (node (ref "U3") (pin "5") (pinfunction "REFIN(+)_5") (pintype "passive+no_connect"))
    )
    (net (code "95") (name "unconnected-(U3-REFIN(-)-Pad6)") (class "Default")
      (node (ref "U3") (pin "6") (pinfunction "REFIN(-)_6") (pintype "passive+no_connect"))
    )
    (net (code "96") (name "unconnected-(U3-VIN(+)-Pad11)") (class "Default")
      (node (ref "U3") (pin "11") (pinfunction "VIN(+)_11") (pintype "passive+no_connect"))
    )
    (net (code "97") (name "unconnected-(U3-VIN(-)-Pad12)") (class "Default")
      (node (ref "U3") (pin "12") (pinfunction "VIN(-)_12") (pintype "passive+no_connect"))
    )
  )
)
